# scHnRk_6b.net
KiCad netlist of a schematic drawn in EAGLE
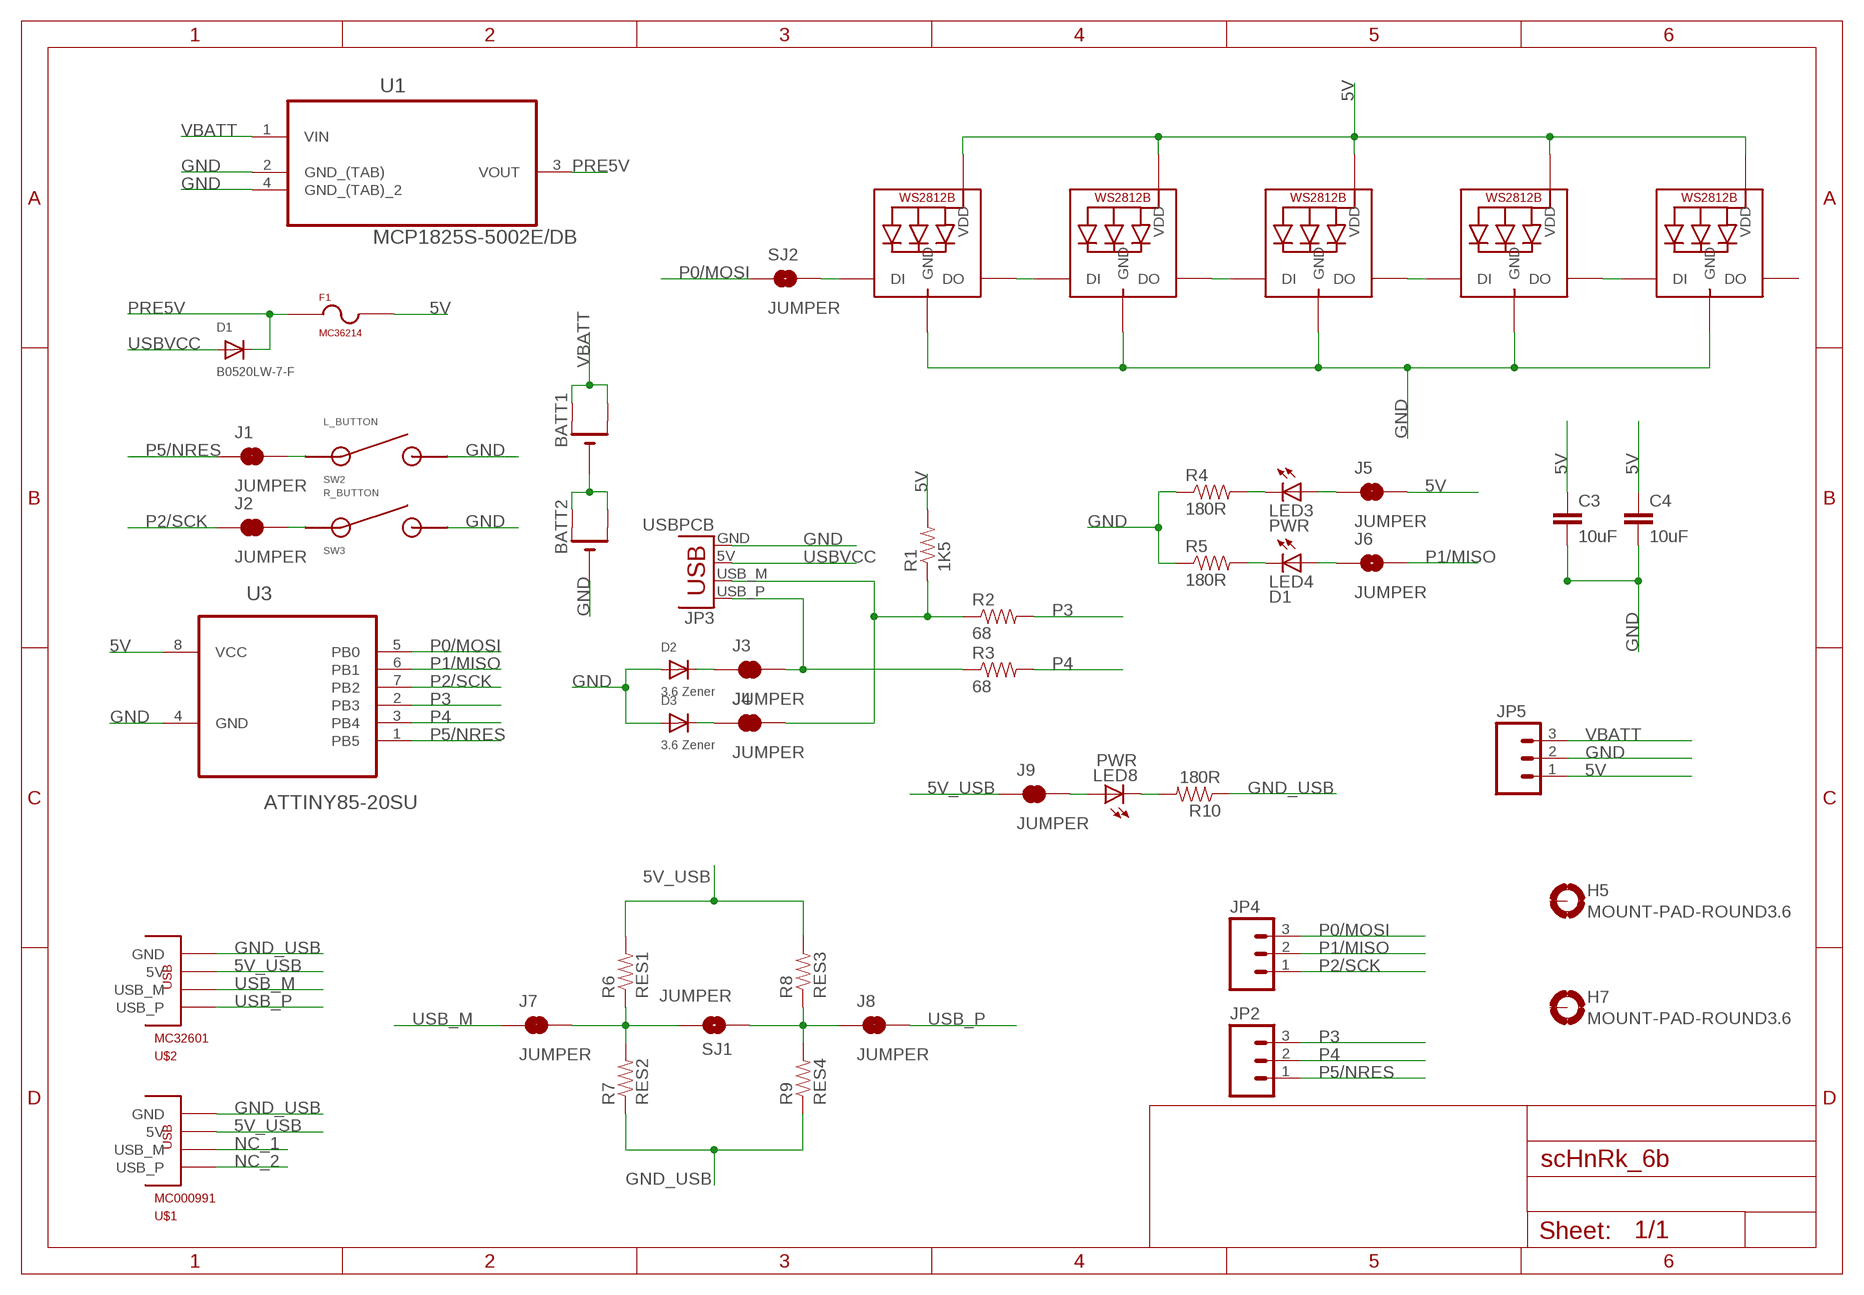
[diagram p0: schematic, sheet 1]

(export (version "E")
  (design (tool "Eeschema 10.0.6"))
  (components
    (comp (ref "BATT1")
      (value "CR2032SMT")
      (footprint "eagle-import:CR2032-SMD")
      (libsource (lib "eagle-import") (part "CR2032SMT"))
    )
    (comp (ref "BATT2")
      (value "CR2032SMT")
      (footprint "eagle-import:CR2032-SMD")
      (libsource (lib "eagle-import") (part "CR2032SMT"))
    )
    (comp (ref "C3")
      (value "10uF")
      (footprint "eagle-import:0805")
      (libsource (lib "eagle-import") (part "CAP0805"))
    )
    (comp (ref "C4")
      (value "10uF")
      (footprint "eagle-import:0805")
      (libsource (lib "eagle-import") (part "CAP0805"))
    )
    (comp (ref "D1")
      (value "B0520LW-7-F")
      (footprint "eagle-import:SOD-123")
      (libsource (lib "eagle-import") (part "DIODESOD-123"))
    )
    (comp (ref "D2")
      (value "3.6 Zener")
      (footprint "eagle-import:SOD-523")
      (libsource (lib "eagle-import") (part "DIODESOD-523"))
    )
    (comp (ref "D3")
      (value "3.6 Zener")
      (footprint "eagle-import:SOD-523")
      (libsource (lib "eagle-import") (part "DIODESOD-523"))
    )
    (comp (ref "F1")
      (value "MC36214")
      (footprint "eagle-import:MC36214")
      (libsource (lib "eagle-import") (part "MC36214"))
    )
    (comp (ref "H5")
      (value "MOUNT-PAD-ROUND3.6")
      (footprint "eagle-import:3,6-PAD")
      (libsource (lib "eagle-import") (part "MOUNT-PAD-ROUND3.6"))
    )
    (comp (ref "H7")
      (value "MOUNT-PAD-ROUND3.6")
      (footprint "eagle-import:3,6-PAD")
      (libsource (lib "eagle-import") (part "MOUNT-PAD-ROUND3.6"))
    )
    (comp (ref "J1")
      (value "JUMPER")
      (footprint "eagle-import:PAD-JUMPER-2-NC_BY_TRACE_YES_SILK")
      (libsource (lib "eagle-import") (part "JUMPER-PAD-2-NC_BY_TRACE"))
    )
    (comp (ref "J2")
      (value "JUMPER")
      (footprint "eagle-import:PAD-JUMPER-2-NC_BY_TRACE_YES_SILK")
      (libsource (lib "eagle-import") (part "JUMPER-PAD-2-NC_BY_TRACE"))
    )
    (comp (ref "J3")
      (value "JUMPER")
      (footprint "eagle-import:PAD-JUMPER-2-NC_BY_TRACE_YES_SILK")
      (libsource (lib "eagle-import") (part "JUMPER-PAD-2-NC_BY_TRACE"))
    )
    (comp (ref "J4")
      (value "JUMPER")
      (footprint "eagle-import:PAD-JUMPER-2-NC_BY_TRACE_YES_SILK")
      (libsource (lib "eagle-import") (part "JUMPER-PAD-2-NC_BY_TRACE"))
    )
    (comp (ref "J5")
      (value "JUMPER")
      (footprint "eagle-import:PAD-JUMPER-2-NC_BY_TRACE_YES_SILK")
      (libsource (lib "eagle-import") (part "JUMPER-PAD-2-NC_BY_TRACE"))
    )
    (comp (ref "J6")
      (value "JUMPER")
      (footprint "eagle-import:PAD-JUMPER-2-NO_YES_SILK")
      (libsource (lib "eagle-import") (part "JUMPER-PAD-2-NOYES_SILK"))
    )
    (comp (ref "J7")
      (value "JUMPER")
      (footprint "eagle-import:PAD-JUMPER-2-NC_BY_TRACE_YES_SILK")
      (libsource (lib "eagle-import") (part "JUMPER-PAD-2-NC_BY_TRACE"))
    )
    (comp (ref "J8")
      (value "JUMPER")
      (footprint "eagle-import:PAD-JUMPER-2-NC_BY_TRACE_YES_SILK")
      (libsource (lib "eagle-import") (part "JUMPER-PAD-2-NC_BY_TRACE"))
    )
    (comp (ref "J9")
      (value "JUMPER")
      (footprint "eagle-import:PAD-JUMPER-2-NC_BY_TRACE_YES_SILK")
      (libsource (lib "eagle-import") (part "JUMPER-PAD-2-NC_BY_TRACE"))
    )
    (comp (ref "JP2")
      (value "M031X03_NO_SILK")
      (footprint "eagle-import:1X03_NO_SILK")
      (libsource (lib "eagle-import") (part "M031X03_NO_SILK"))
    )
    (comp (ref "JP3")
      (value "USBPCB")
      (footprint "eagle-import:USB-A-PCB")
      (libsource (lib "eagle-import") (part "USBPCB"))
    )
    (comp (ref "JP4")
      (value "M031X03_NO_SILK")
      (footprint "eagle-import:1X03_NO_SILK")
      (libsource (lib "eagle-import") (part "M031X03_NO_SILK"))
    )
    (comp (ref "JP5")
      (value "M031X03_NO_SILK")
      (footprint "eagle-import:1X03_NO_SILK")
      (libsource (lib "eagle-import") (part "M031X03_NO_SILK"))
    )
    (comp (ref "LED1")
      (value "WS2812B5050")
      (footprint "eagle-import:WS2812B")
      (libsource (lib "eagle-import") (part "WS2812B5050"))
    )
    (comp (ref "LED2")
      (value "WS2812B5050")
      (footprint "eagle-import:WS2812B")
      (libsource (lib "eagle-import") (part "WS2812B5050"))
    )
    (comp (ref "LED3")
      (value "PWR")
      (footprint "eagle-import:CHIPLED_0603")
      (libsource (lib "eagle-import") (part "LEDCHIPLED_0603"))
    )
    (comp (ref "LED4")
      (value "D1")
      (footprint "eagle-import:CHIPLED_0603")
      (libsource (lib "eagle-import") (part "LEDCHIPLED_0603"))
    )
    (comp (ref "LED5")
      (value "WS2812B5050")
      (footprint "eagle-import:WS2812B")
      (libsource (lib "eagle-import") (part "WS2812B5050"))
    )
    (comp (ref "LED6")
      (value "WS2812B5050")
      (footprint "eagle-import:WS2812B")
      (libsource (lib "eagle-import") (part "WS2812B5050"))
    )
    (comp (ref "LED7")
      (value "WS2812B5050")
      (footprint "eagle-import:WS2812B")
      (libsource (lib "eagle-import") (part "WS2812B5050"))
    )
    (comp (ref "LED8")
      (value "PWR")
      (footprint "eagle-import:CHIPLED_0603")
      (libsource (lib "eagle-import") (part "LEDCHIPLED_0603"))
    )
    (comp (ref "R1")
      (value "1K5")
      (footprint "eagle-import:0805")
      (libsource (lib "eagle-import") (part "RESISTOR0805-RES"))
    )
    (comp (ref "R2")
      (value "68")
      (footprint "eagle-import:0805")
      (libsource (lib "eagle-import") (part "RESISTOR0805-RES"))
    )
    (comp (ref "R3")
      (value "68")
      (footprint "eagle-import:0805")
      (libsource (lib "eagle-import") (part "RESISTOR0805-RES"))
    )
    (comp (ref "R4")
      (value "180R")
      (footprint "eagle-import:0805")
      (libsource (lib "eagle-import") (part "RESISTOR0805-RES"))
    )
    (comp (ref "R5")
      (value "180R")
      (footprint "eagle-import:0805")
      (libsource (lib "eagle-import") (part "RESISTOR0805-RES"))
    )
    (comp (ref "R6")
      (value "RES1")
      (footprint "eagle-import:0805")
      (libsource (lib "eagle-import") (part "RESISTOR0805-RES"))
    )
    (comp (ref "R7")
      (value "RES2")
      (footprint "eagle-import:0805")
      (libsource (lib "eagle-import") (part "RESISTOR0805-RES"))
    )
    (comp (ref "R8")
      (value "RES3")
      (footprint "eagle-import:0805")
      (libsource (lib "eagle-import") (part "RESISTOR0805-RES"))
    )
    (comp (ref "R9")
      (value "RES4")
      (footprint "eagle-import:0805")
      (libsource (lib "eagle-import") (part "RESISTOR0805-RES"))
    )
    (comp (ref "R10")
      (value "180R")
      (footprint "eagle-import:0805")
      (libsource (lib "eagle-import") (part "RESISTOR0805-RES"))
    )
    (comp (ref "SJ1")
      (value "JUMPER")
      (footprint "eagle-import:PAD-JUMPER-2-NO_YES_SILK")
      (libsource (lib "eagle-import") (part "JUMPER-PAD-2-NOYES_SILK"))
    )
    (comp (ref "SJ2")
      (value "JUMPER")
      (footprint "eagle-import:PAD-JUMPER-2-NO_YES_SILK")
      (libsource (lib "eagle-import") (part "JUMPER-PAD-2-NOYES_SILK"))
    )
    (comp (ref "SW2")
      (value "L_BUTTON")
      (footprint "eagle-import:SKRBAGE010")
      (libsource (lib "eagle-import") (part "SKRBAGE010"))
    )
    (comp (ref "SW3")
      (value "R_BUTTON")
      (footprint "eagle-import:SKRBAGE010")
      (libsource (lib "eagle-import") (part "SKRBAGE010"))
    )
    (comp (ref "U$1")
      (value "MC000991")
      (footprint "eagle-import:MC000991")
      (libsource (lib "eagle-import") (part "MC000991"))
    )
    (comp (ref "U$2")
      (value "MC32601")
      (footprint "eagle-import:MC32601")
      (libsource (lib "eagle-import") (part "MC32601"))
    )
    (comp (ref "U1")
      (value "MCP1825S-5002E/DB")
      (footprint "eagle-import:SOT230P700X180-4N")
      (libsource (lib "eagle-import") (part "MCP1825S-5002E/DB"))
    )
    (comp (ref "U3")
      (value "ATTINY85-20SU")
      (footprint "eagle-import:SOIC127P798X216-8N")
      (libsource (lib "eagle-import") (part "ATTINY85-20SU"))
    )
  )
  (nets
    (net (code "1") (name "/5V") (class "Default")
      (node (ref "C3") (pin "1") (pinfunction "1_1") (pintype "passive"))
      (node (ref "C4") (pin "1") (pinfunction "1_1") (pintype "passive"))
      (node (ref "F1") (pin "P$2") (pinfunction "P$2_P$2") (pintype "bidirectional"))
      (node (ref "J5") (pin "2") (pinfunction "2_2") (pintype "passive"))
      (node (ref "JP5") (pin "1") (pinfunction "1_1") (pintype "passive"))
      (node (ref "LED1") (pin "1-VDD") (pinfunction "VDD_1-VDD") (pintype "power_in"))
      (node (ref "LED2") (pin "1-VDD") (pinfunction "VDD_1-VDD") (pintype "power_in"))
      (node (ref "LED5") (pin "1-VDD") (pinfunction "VDD_1-VDD") (pintype "power_in"))
      (node (ref "LED6") (pin "1-VDD") (pinfunction "VDD_1-VDD") (pintype "power_in"))
      (node (ref "LED7") (pin "1-VDD") (pinfunction "VDD_1-VDD") (pintype "power_in"))
      (node (ref "R1") (pin "2") (pinfunction "2_2") (pintype "passive"))
      (node (ref "U3") (pin "8") (pinfunction "VCC_8") (pintype "power_in"))
    )
    (net (code "2") (name "/5V_USB") (class "Default")
      (node (ref "J9") (pin "1") (pinfunction "1_1") (pintype "passive"))
      (node (ref "R6") (pin "2") (pinfunction "2_2") (pintype "passive"))
      (node (ref "R8") (pin "2") (pinfunction "2_2") (pintype "passive"))
      (node (ref "U$1") (pin "P$4") (pinfunction "5V_P$4") (pintype "bidirectional"))
      (node (ref "U$2") (pin "P$2") (pinfunction "5V_P$2") (pintype "bidirectional"))
    )
    (net (code "3") (name "/GND") (class "Default")
      (node (ref "BATT2") (pin "-") (pinfunction "-_-") (pintype "passive"))
      (node (ref "C3") (pin "2") (pinfunction "2_2") (pintype "passive"))
      (node (ref "C4") (pin "2") (pinfunction "2_2") (pintype "passive"))
      (node (ref "D2") (pin "A") (pinfunction "A_A") (pintype "passive"))
      (node (ref "D3") (pin "A") (pinfunction "A_A") (pintype "passive"))
      (node (ref "JP3") (pin "GND") (pinfunction "GND_GND") (pintype "bidirectional"))
      (node (ref "JP5") (pin "2") (pinfunction "2_2") (pintype "passive"))
      (node (ref "LED1") (pin "3-GND") (pinfunction "GND_3-GND") (pintype "power_in"))
      (node (ref "LED2") (pin "3-GND") (pinfunction "GND_3-GND") (pintype "power_in"))
      (node (ref "LED5") (pin "3-GND") (pinfunction "GND_3-GND") (pintype "power_in"))
      (node (ref "LED6") (pin "3-GND") (pinfunction "GND_3-GND") (pintype "power_in"))
      (node (ref "LED7") (pin "3-GND") (pinfunction "GND_3-GND") (pintype "power_in"))
      (node (ref "R4") (pin "1") (pinfunction "1_1") (pintype "passive"))
      (node (ref "R5") (pin "1") (pinfunction "1_1") (pintype "passive"))
      (node (ref "SW2") (pin "P$2") (pinfunction "P$2_P$2") (pintype "bidirectional"))
      (node (ref "SW2") (pin "P$4") (pinfunction "P$2_P$4") (pintype "bidirectional"))
      (node (ref "SW3") (pin "P$2") (pinfunction "P$2_P$2") (pintype "bidirectional"))
      (node (ref "SW3") (pin "P$4") (pinfunction "P$2_P$4") (pintype "bidirectional"))
      (node (ref "U1") (pin "2") (pinfunction "GND_(TAB)_2") (pintype "passive"))
      (node (ref "U1") (pin "4") (pinfunction "GND_(TAB)_2_4") (pintype "passive"))
      (node (ref "U3") (pin "4") (pinfunction "GND_4") (pintype "passive"))
    )
    (net (code "4") (name "/GND_USB") (class "Default")
      (node (ref "R10") (pin "1") (pinfunction "1_1") (pintype "passive"))
      (node (ref "R7") (pin "1") (pinfunction "1_1") (pintype "passive"))
      (node (ref "R9") (pin "1") (pinfunction "1_1") (pintype "passive"))
      (node (ref "U$1") (pin "P$1") (pinfunction "GND_P$1") (pintype "bidirectional"))
      (node (ref "U$2") (pin "P$5") (pinfunction "GND_P$5") (pintype "bidirectional"))
    )
    (net (code "5") (name "/NC_1") (class "Default")
      (node (ref "U$1") (pin "P$3") (pinfunction "USB_M_P$3") (pintype "bidirectional"))
    )
    (net (code "6") (name "/NC_2") (class "Default")
      (node (ref "U$1") (pin "P$2") (pinfunction "USB_P_P$2") (pintype "bidirectional"))
    )
    (net (code "7") (name "/P0{slash}MOSI") (class "Default")
      (node (ref "JP4") (pin "3") (pinfunction "3_3") (pintype "passive"))
      (node (ref "SJ2") (pin "1") (pinfunction "1_1") (pintype "passive"))
      (node (ref "U3") (pin "5") (pinfunction "PB0_5") (pintype "bidirectional"))
    )
    (net (code "8") (name "/P1{slash}MISO") (class "Default")
      (node (ref "J6") (pin "2") (pinfunction "2_2") (pintype "passive"))
      (node (ref "JP4") (pin "2") (pinfunction "2_2") (pintype "passive"))
      (node (ref "U3") (pin "6") (pinfunction "PB1_6") (pintype "bidirectional"))
    )
    (net (code "9") (name "/P2{slash}SCK") (class "Default")
      (node (ref "J2") (pin "1") (pinfunction "1_1") (pintype "passive"))
      (node (ref "JP4") (pin "1") (pinfunction "1_1") (pintype "passive"))
      (node (ref "U3") (pin "7") (pinfunction "PB2_7") (pintype "bidirectional"))
    )
    (net (code "10") (name "/P3") (class "Default")
      (node (ref "JP2") (pin "3") (pinfunction "3_3") (pintype "passive"))
      (node (ref "R2") (pin "2") (pinfunction "2_2") (pintype "passive"))
      (node (ref "U3") (pin "2") (pinfunction "PB3_2") (pintype "bidirectional"))
    )
    (net (code "11") (name "/P4") (class "Default")
      (node (ref "JP2") (pin "2") (pinfunction "2_2") (pintype "passive"))
      (node (ref "R3") (pin "2") (pinfunction "2_2") (pintype "passive"))
      (node (ref "U3") (pin "3") (pinfunction "PB4_3") (pintype "bidirectional"))
    )
    (net (code "12") (name "/P5{slash}NRES") (class "Default")
      (node (ref "J1") (pin "1") (pinfunction "1_1") (pintype "passive"))
      (node (ref "JP2") (pin "1") (pinfunction "1_1") (pintype "passive"))
      (node (ref "U3") (pin "1") (pinfunction "PB5_1") (pintype "bidirectional"))
    )
    (net (code "13") (name "/PRE5V") (class "Default")
      (node (ref "D1") (pin "C") (pinfunction "C_C") (pintype "passive"))
      (node (ref "F1") (pin "P$1") (pinfunction "P$1_P$1") (pintype "bidirectional"))
      (node (ref "U1") (pin "3") (pinfunction "VOUT_3") (pintype "output"))
    )
    (net (code "14") (name "/USBVCC") (class "Default")
      (node (ref "D1") (pin "A") (pinfunction "A_A") (pintype "passive"))
      (node (ref "JP3") (pin "5V") (pinfunction "VBUS_5V") (pintype "bidirectional"))
    )
    (net (code "15") (name "/USB_M") (class "Default")
      (node (ref "J7") (pin "1") (pinfunction "1_1") (pintype "passive"))
      (node (ref "U$2") (pin "P$3") (pinfunction "USB_M_P$3") (pintype "bidirectional"))
    )
    (net (code "16") (name "/USB_P") (class "Default")
      (node (ref "J8") (pin "2") (pinfunction "2_2") (pintype "passive"))
      (node (ref "U$2") (pin "P$4") (pinfunction "USB_P_P$4") (pintype "bidirectional"))
    )
    (net (code "17") (name "/VBATT") (class "Default")
      (node (ref "BATT1") (pin "+$1") (pinfunction "+_+$1") (pintype "passive"))
      (node (ref "BATT1") (pin "+$2") (pinfunction "+1_+$2") (pintype "passive"))
      (node (ref "JP5") (pin "3") (pinfunction "3_3") (pintype "passive"))
      (node (ref "U1") (pin "1") (pinfunction "VIN_1") (pintype "input"))
    )
    (net (code "18") (name "Net-(BATT2-+)") (class "Default")
      (node (ref "BATT1") (pin "-") (pinfunction "-_-") (pintype "passive"))
      (node (ref "BATT2") (pin "+$1") (pinfunction "+_+$1") (pintype "passive"))
      (node (ref "BATT2") (pin "+$2") (pinfunction "+1_+$2") (pintype "passive"))
    )
    (net (code "19") (name "Net-(D2-C)") (class "Default")
      (node (ref "D2") (pin "K") (pinfunction "C_K") (pintype "passive"))
      (node (ref "J3") (pin "1") (pinfunction "1_1") (pintype "passive"))
    )
    (net (code "20") (name "Net-(D3-C)") (class "Default")
      (node (ref "D3") (pin "K") (pinfunction "C_K") (pintype "passive"))
      (node (ref "J4") (pin "1") (pinfunction "1_1") (pintype "passive"))
    )
    (net (code "21") (name "Net-(J1-Pad2)") (class "Default")
      (node (ref "J1") (pin "2") (pinfunction "2_2") (pintype "passive"))
      (node (ref "SW2") (pin "P$1") (pinfunction "P$1_P$1") (pintype "bidirectional"))
      (node (ref "SW2") (pin "P$3") (pinfunction "P$1_P$3") (pintype "bidirectional"))
    )
    (net (code "22") (name "Net-(J2-Pad2)") (class "Default")
      (node (ref "J2") (pin "2") (pinfunction "2_2") (pintype "passive"))
      (node (ref "SW3") (pin "P$1") (pinfunction "P$1_P$1") (pintype "bidirectional"))
      (node (ref "SW3") (pin "P$3") (pinfunction "P$1_P$3") (pintype "bidirectional"))
    )
    (net (code "23") (name "Net-(J5-Pad1)") (class "Default")
      (node (ref "J5") (pin "1") (pinfunction "1_1") (pintype "passive"))
      (node (ref "LED3") (pin "A") (pinfunction "A_A") (pintype "passive"))
    )
    (net (code "24") (name "Net-(J6-Pad1)") (class "Default")
      (node (ref "J6") (pin "1") (pinfunction "1_1") (pintype "passive"))
      (node (ref "LED4") (pin "A") (pinfunction "A_A") (pintype "passive"))
    )
    (net (code "25") (name "Net-(J7-Pad2)") (class "Default")
      (node (ref "J7") (pin "2") (pinfunction "2_2") (pintype "passive"))
      (node (ref "R6") (pin "1") (pinfunction "1_1") (pintype "passive"))
      (node (ref "R7") (pin "2") (pinfunction "2_2") (pintype "passive"))
      (node (ref "SJ1") (pin "2") (pinfunction "2_2") (pintype "passive"))
    )
    (net (code "26") (name "Net-(J8-Pad1)") (class "Default")
      (node (ref "J8") (pin "1") (pinfunction "1_1") (pintype "passive"))
      (node (ref "R8") (pin "1") (pinfunction "1_1") (pintype "passive"))
      (node (ref "R9") (pin "2") (pinfunction "2_2") (pintype "passive"))
      (node (ref "SJ1") (pin "1") (pinfunction "1_1") (pintype "passive"))
    )
    (net (code "27") (name "Net-(J9-Pad2)") (class "Default")
      (node (ref "J9") (pin "2") (pinfunction "2_2") (pintype "passive"))
      (node (ref "LED8") (pin "A") (pinfunction "A_A") (pintype "passive"))
    )
    (net (code "28") (name "Net-(JP3-D+)") (class "Default")
      (node (ref "J3") (pin "2") (pinfunction "2_2") (pintype "passive"))
      (node (ref "JP3") (pin "USB_P") (pinfunction "D+_USB_P") (pintype "bidirectional"))
      (node (ref "R3") (pin "1") (pinfunction "1_1") (pintype "passive"))
    )
    (net (code "29") (name "Net-(JP3-D-)") (class "Default")
      (node (ref "J4") (pin "2") (pinfunction "2_2") (pintype "passive"))
      (node (ref "JP3") (pin "USB_M") (pinfunction "D-_USB_M") (pintype "bidirectional"))
      (node (ref "R1") (pin "1") (pinfunction "1_1") (pintype "passive"))
      (node (ref "R2") (pin "1") (pinfunction "1_1") (pintype "passive"))
    )
    (net (code "30") (name "Net-(LED1-DI)") (class "Default")
      (node (ref "LED1") (pin "4-DIN") (pinfunction "DI_4-DIN") (pintype "input"))
      (node (ref "SJ2") (pin "2") (pinfunction "2_2") (pintype "passive"))
    )
    (net (code "31") (name "Net-(LED1-DO)") (class "Default")
      (node (ref "LED1") (pin "2-DOUT") (pinfunction "DO_2-DOUT") (pintype "output"))
      (node (ref "LED2") (pin "4-DIN") (pinfunction "DI_4-DIN") (pintype "input"))
    )
    (net (code "32") (name "Net-(LED2-DO)") (class "Default")
      (node (ref "LED2") (pin "2-DOUT") (pinfunction "DO_2-DOUT") (pintype "output"))
      (node (ref "LED5") (pin "4-DIN") (pinfunction "DI_4-DIN") (pintype "input"))
    )
    (net (code "33") (name "Net-(LED3-PadC)") (class "Default")
      (node (ref "LED3") (pin "C") (pinfunction "C_C") (pintype "passive"))
      (node (ref "R4") (pin "2") (pinfunction "2_2") (pintype "passive"))
    )
    (net (code "34") (name "Net-(LED4-PadC)") (class "Default")
      (node (ref "LED4") (pin "C") (pinfunction "C_C") (pintype "passive"))
      (node (ref "R5") (pin "2") (pinfunction "2_2") (pintype "passive"))
    )
    (net (code "35") (name "Net-(LED5-DO)") (class "Default")
      (node (ref "LED5") (pin "2-DOUT") (pinfunction "DO_2-DOUT") (pintype "output"))
      (node (ref "LED6") (pin "4-DIN") (pinfunction "DI_4-DIN") (pintype "input"))
    )
    (net (code "36") (name "Net-(LED6-DO)") (class "Default")
      (node (ref "LED6") (pin "2-DOUT") (pinfunction "DO_2-DOUT") (pintype "output"))
      (node (ref "LED7") (pin "4-DIN") (pinfunction "DI_4-DIN") (pintype "input"))
    )
    (net (code "37") (name "Net-(LED8-PadC)") (class "Default")
      (node (ref "LED8") (pin "C") (pinfunction "C_C") (pintype "passive"))
      (node (ref "R10") (pin "2") (pinfunction "2_2") (pintype "passive"))
    )
    (net (code "38") (name "unconnected-(H5-MOUNT-PadB3,6)") (class "Default")
      (node (ref "H5") (pin "B3,6") (pinfunction "MOUNT_B3,6") (pintype "passive"))
    )
    (net (code "39") (name "unconnected-(H7-MOUNT-PadB3,6)") (class "Default")
      (node (ref "H7") (pin "B3,6") (pinfunction "MOUNT_B3,6") (pintype "passive"))
    )
    (net (code "40") (name "unconnected-(LED7-DO-Pad2-DOUT)") (class "Default")
      (node (ref "LED7") (pin "2-DOUT") (pinfunction "DO_2-DOUT") (pintype "output"))
    )
  )
)
